# ESP32Shield.net
KiCad netlist of a schematic drawn in EAGLE
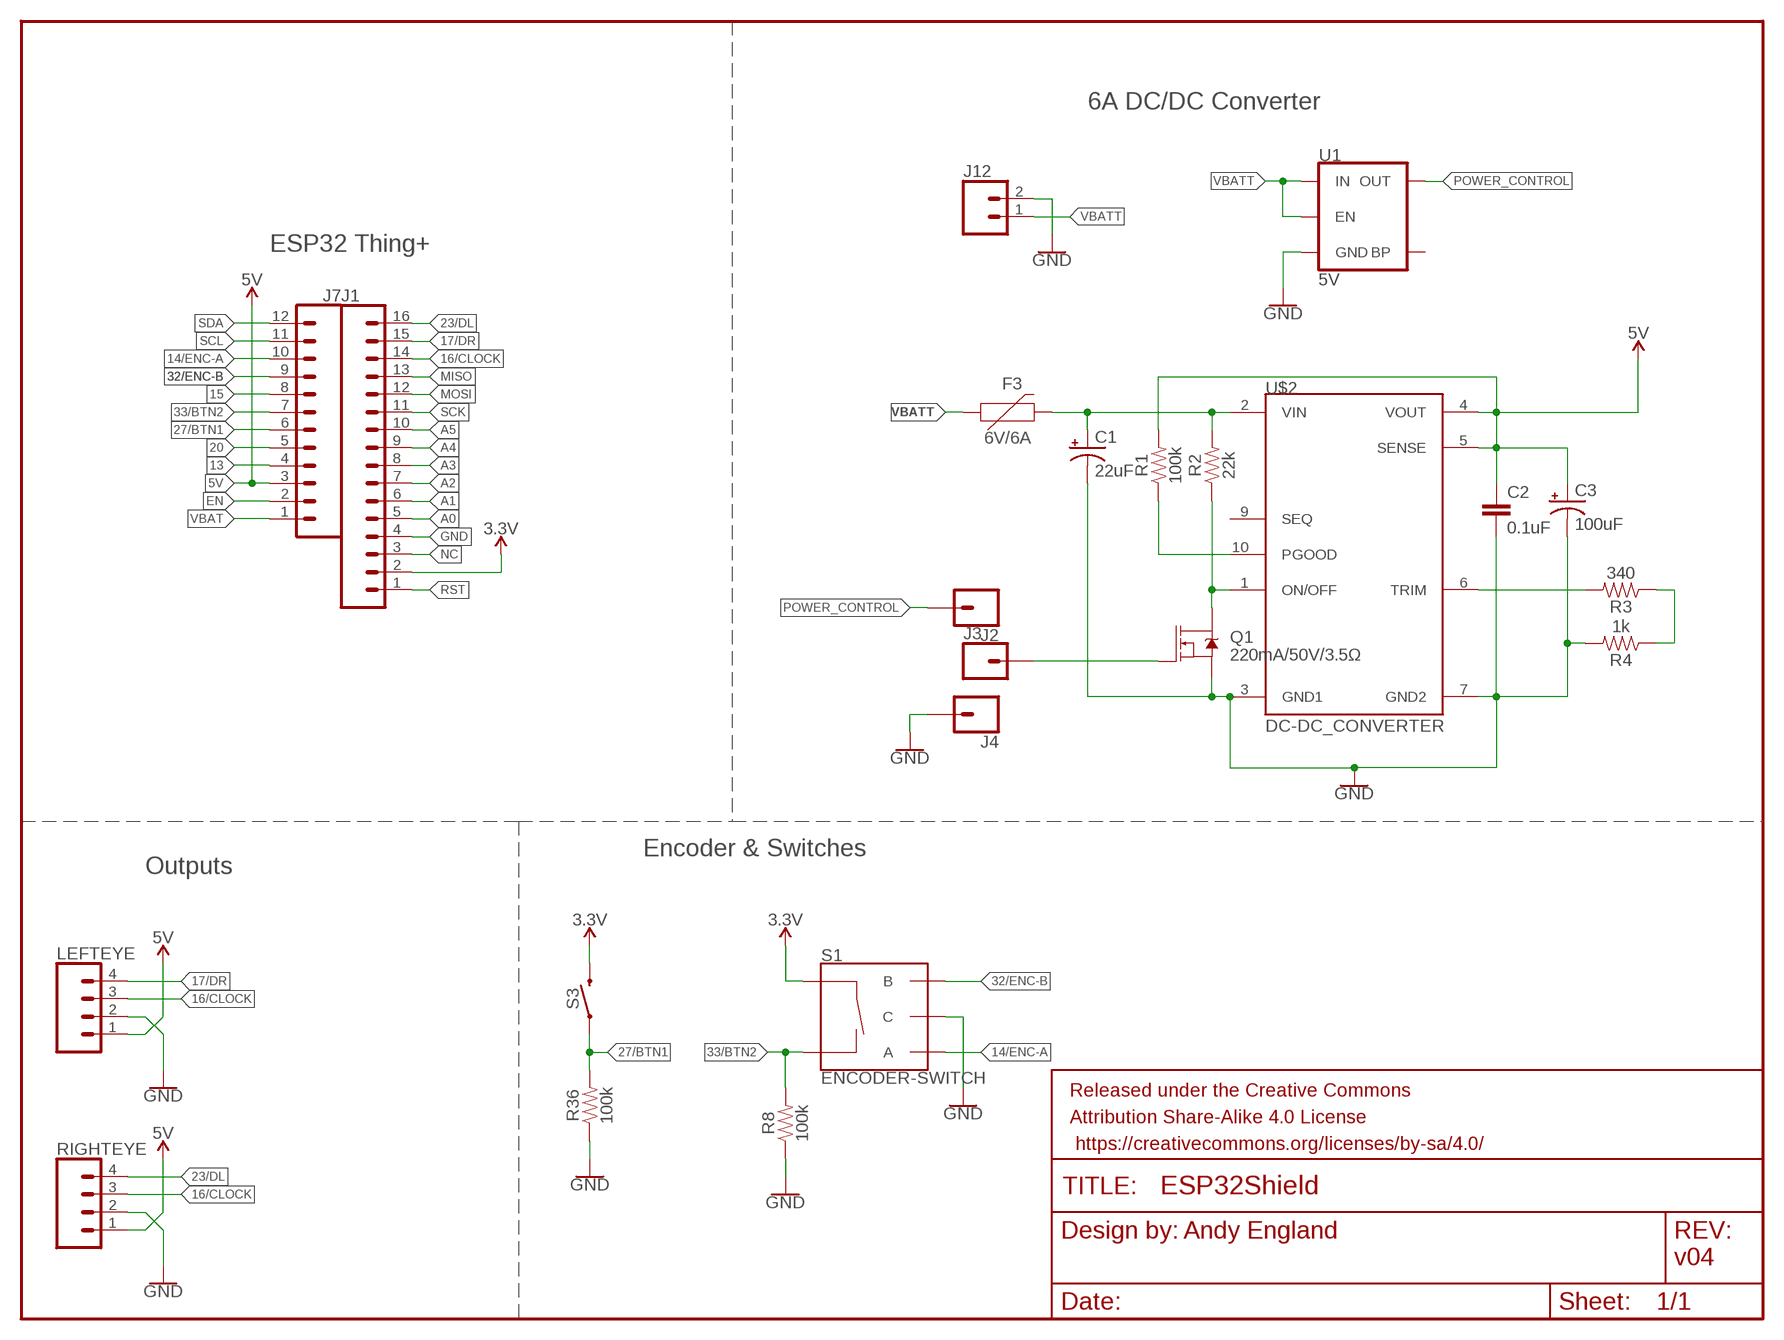
[diagram p0: schematic, sheet 1]

(export (version "E")
  (design (tool "Eeschema 10.0.6"))
  (components
    (comp (ref "C1")
      (value "22uF")
      (footprint "eagle-import:PANASONIC_C")
      (libsource (lib "eagle-import") (part "22UF-POLAR-PANASONIC_C-35V-20%"))
    )
    (comp (ref "C2")
      (value "0.1uF")
      (footprint "eagle-import:0603")
      (libsource (lib "eagle-import") (part "0.1UF-0603-25V-5%"))
    )
    (comp (ref "C3")
      (value "100uF")
      (footprint "eagle-import:PANASONIC_D")
      (libsource (lib "eagle-import") (part "100UF-POLAR-25V-20%(ELEC)"))
    )
    (comp (ref "F3")
      (value "6V/6A")
      (footprint "eagle-import:1206")
      (libsource (lib "eagle-import") (part "PPTC_HALF-AMP"))
    )
    (comp (ref "FRAME1")
      (value "FRAME-LETTER")
      (footprint "eagle-import:CREATIVE_COMMONS")
      (libsource (lib "eagle-import") (part "FRAME-LETTER"))
    )
    (comp (ref "J1")
      (value "CONN_161X16_NO_SILK")
      (footprint "eagle-import:1X16_NO_SILK")
      (libsource (lib "eagle-import") (part "CONN_161X16_NO_SILK"))
    )
    (comp (ref "J2")
      (value "CONN_01")
      (footprint "eagle-import:1X01")
      (libsource (lib "eagle-import") (part "CONN_01"))
    )
    (comp (ref "J3")
      (value "CONN_01")
      (footprint "eagle-import:1X01")
      (libsource (lib "eagle-import") (part "CONN_01"))
    )
    (comp (ref "J4")
      (value "CONN_01")
      (footprint "eagle-import:1X01")
      (libsource (lib "eagle-import") (part "CONN_01"))
    )
    (comp (ref "J7")
      (value "CONN_12NO_SILK")
      (footprint "eagle-import:1X12_NO_SILK")
      (libsource (lib "eagle-import") (part "CONN_12NO_SILK"))
    )
    (comp (ref "J12")
      (value "CONN_025MM")
      (footprint "eagle-import:SCREWTERMINAL-5MM-2")
      (libsource (lib "eagle-import") (part "CONN_025MM"))
    )
    (comp (ref "LEFTEYE")
      (value "CONN_041X04_NO_SILK")
      (footprint "eagle-import:1X04_NO_SILK")
      (libsource (lib "eagle-import") (part "CONN_041X04_NO_SILK"))
    )
    (comp (ref "Q1")
      (value "220mA/50V/3.5Ω")
      (footprint "eagle-import:SOT23-3")
      (libsource (lib "eagle-import") (part "MOSFET-NCH-BSS138"))
    )
    (comp (ref "R1")
      (value "100k")
      (footprint "eagle-import:0603")
      (libsource (lib "eagle-import") (part "100KOHM-0603-1/10W-1%"))
    )
    (comp (ref "R2")
      (value "22k")
      (footprint "eagle-import:0603")
      (libsource (lib "eagle-import") (part "22KOHM-0603-1/10W-1%"))
    )
    (comp (ref "R3")
      (value "340")
      (footprint "eagle-import:0603")
      (libsource (lib "eagle-import") (part "340OHM-0603-1/10W-1%"))
    )
    (comp (ref "R4")
      (value "1k")
      (footprint "eagle-import:0603")
      (libsource (lib "eagle-import") (part "1KOHM-0603-1/10W-1%"))
    )
    (comp (ref "R8")
      (value "100k")
      (footprint "eagle-import:0603")
      (libsource (lib "eagle-import") (part "100KOHM-0603-1/10W-1%"))
    )
    (comp (ref "R36")
      (value "100k")
      (footprint "eagle-import:0603")
      (libsource (lib "eagle-import") (part "100KOHM-0603-1/10W-1%"))
    )
    (comp (ref "RIGHTEYE")
      (value "CONN_041X04_NO_SILK")
      (footprint "eagle-import:1X04_NO_SILK")
      (libsource (lib "eagle-import") (part "CONN_041X04_NO_SILK"))
    )
    (comp (ref "S1")
      (value "ENCODER-SWITCH")
      (footprint "eagle-import:ROTARY_ENC_PLAIN")
      (libsource (lib "eagle-import") (part "ENCODER-SWITCH"))
    )
    (comp (ref "S3")
      (value "MOMENTARY-SWITCH-SPST-SMD-5.2-REDUNDANT")
      (footprint "eagle-import:TACTILE_SWITCH_SMD_5.2MM")
      (libsource (lib "eagle-import") (part "MOMENTARY-SWITCH-SPST-SMD-5.2-REDUNDANT"))
    )
    (comp (ref "U$2")
      (value "DC-DC_CONVERTER")
      (footprint "eagle-import:DC-DC_CONVERTER")
      (libsource (lib "eagle-import") (part "DC-DC_CONVERTER"))
    )
    (comp (ref "U1")
      (value "5V")
      (footprint "eagle-import:SOT23-5")
      (libsource (lib "eagle-import") (part "V_REG_MIC52055V"))
    )
  )
  (nets
    (net (code "1") (name "3.3V") (class "Default")
      (node (ref "J1") (pin "2") (pinfunction "2_2") (pintype "passive"))
      (node (ref "S1") (pin "SW+") (pinfunction "SW+_SW+") (pintype "bidirectional"))
      (node (ref "S3") (pin "3") (pinfunction "2_3") (pintype "passive"))
      (node (ref "S3") (pin "4") (pinfunction "2_4") (pintype "passive"))
    )
    (net (code "2") (name "5V") (class "Default")
      (node (ref "C2") (pin "1") (pinfunction "1_1") (pintype "passive"))
      (node (ref "C3") (pin "+") (pinfunction "+_+") (pintype "passive"))
      (node (ref "J7") (pin "3") (pinfunction "3_3") (pintype "passive"))
      (node (ref "LEFTEYE") (pin "1") (pinfunction "1_1") (pintype "passive"))
      (node (ref "R1") (pin "2") (pinfunction "2_2") (pintype "passive"))
      (node (ref "RIGHTEYE") (pin "1") (pinfunction "1_1") (pintype "passive"))
      (node (ref "U$2") (pin "4") (pinfunction "VOUT_4") (pintype "bidirectional"))
      (node (ref "U$2") (pin "5") (pinfunction "SENSE_5") (pintype "bidirectional"))
    )
    (net (code "3") (name "13") (class "Default")
      (node (ref "J7") (pin "4") (pinfunction "4_4") (pintype "passive"))
    )
    (net (code "4") (name "14{slash}ENC-A") (class "Default")
      (node (ref "J7") (pin "10") (pinfunction "10_10") (pintype "passive"))
      (node (ref "S1") (pin "A") (pinfunction "A_A") (pintype "bidirectional"))
    )
    (net (code "5") (name "15") (class "Default")
      (node (ref "J7") (pin "8") (pinfunction "8_8") (pintype "passive"))
    )
    (net (code "6") (name "16{slash}CLOCK") (class "Default")
      (node (ref "J1") (pin "14") (pinfunction "14_14") (pintype "passive"))
      (node (ref "LEFTEYE") (pin "3") (pinfunction "3_3") (pintype "passive"))
      (node (ref "RIGHTEYE") (pin "3") (pinfunction "3_3") (pintype "passive"))
    )
    (net (code "7") (name "17{slash}DR") (class "Default")
      (node (ref "J1") (pin "15") (pinfunction "15_15") (pintype "passive"))
      (node (ref "LEFTEYE") (pin "4") (pinfunction "4_4") (pintype "passive"))
    )
    (net (code "8") (name "20") (class "Default")
      (node (ref "J7") (pin "5") (pinfunction "5_5") (pintype "passive"))
    )
    (net (code "9") (name "23{slash}DL") (class "Default")
      (node (ref "J1") (pin "16") (pinfunction "16_16") (pintype "passive"))
      (node (ref "RIGHTEYE") (pin "4") (pinfunction "4_4") (pintype "passive"))
    )
    (net (code "10") (name "27{slash}BTN1") (class "Default")
      (node (ref "J7") (pin "6") (pinfunction "6_6") (pintype "passive"))
      (node (ref "R36") (pin "2") (pinfunction "2_2") (pintype "passive"))
      (node (ref "S3") (pin "1") (pinfunction "1_1") (pintype "passive"))
      (node (ref "S3") (pin "2") (pinfunction "1_2") (pintype "passive"))
    )
    (net (code "11") (name "32{slash}ENC-B") (class "Default")
      (node (ref "J7") (pin "9") (pinfunction "9_9") (pintype "passive"))
      (node (ref "S1") (pin "B") (pinfunction "B_B") (pintype "bidirectional"))
    )
    (net (code "12") (name "33{slash}BTN2") (class "Default")
      (node (ref "J7") (pin "7") (pinfunction "7_7") (pintype "passive"))
      (node (ref "R8") (pin "2") (pinfunction "2_2") (pintype "passive"))
      (node (ref "S1") (pin "SW-") (pinfunction "SW-_SW-") (pintype "bidirectional"))
    )
    (net (code "13") (name "A0") (class "Default")
      (node (ref "J1") (pin "5") (pinfunction "5_5") (pintype "passive"))
    )
    (net (code "14") (name "A1") (class "Default")
      (node (ref "J1") (pin "6") (pinfunction "6_6") (pintype "passive"))
    )
    (net (code "15") (name "A2") (class "Default")
      (node (ref "J1") (pin "7") (pinfunction "7_7") (pintype "passive"))
    )
    (net (code "16") (name "A3") (class "Default")
      (node (ref "J1") (pin "8") (pinfunction "8_8") (pintype "passive"))
    )
    (net (code "17") (name "A4") (class "Default")
      (node (ref "J1") (pin "9") (pinfunction "9_9") (pintype "passive"))
    )
    (net (code "18") (name "A5") (class "Default")
      (node (ref "J1") (pin "10") (pinfunction "10_10") (pintype "passive"))
    )
    (net (code "19") (name "EN") (class "Default")
      (node (ref "J7") (pin "2") (pinfunction "2_2") (pintype "passive"))
    )
    (net (code "20") (name "GND") (class "Default")
      (node (ref "C1") (pin "-") (pinfunction "-_-") (pintype "passive"))
      (node (ref "C2") (pin "2") (pinfunction "2_2") (pintype "passive"))
      (node (ref "C3") (pin "-") (pinfunction "-_-") (pintype "passive"))
      (node (ref "J1") (pin "4") (pinfunction "4_4") (pintype "passive"))
      (node (ref "J12") (pin "2") (pinfunction "2_2") (pintype "passive"))
      (node (ref "J4") (pin "1") (pinfunction "1_1") (pintype "passive"))
      (node (ref "LEFTEYE") (pin "2") (pinfunction "2_2") (pintype "passive"))
      (node (ref "Q1") (pin "2") (pinfunction "S_2") (pintype "bidirectional"))
      (node (ref "R36") (pin "1") (pinfunction "1_1") (pintype "passive"))
      (node (ref "R4") (pin "2") (pinfunction "2_2") (pintype "passive"))
      (node (ref "R8") (pin "1") (pinfunction "1_1") (pintype "passive"))
      (node (ref "RIGHTEYE") (pin "2") (pinfunction "2_2") (pintype "passive"))
      (node (ref "S1") (pin "C") (pinfunction "C_C") (pintype "bidirectional"))
      (node (ref "U$2") (pin "3") (pinfunction "GND1_3") (pintype "bidirectional"))
      (node (ref "U$2") (pin "7") (pinfunction "GND2_7") (pintype "bidirectional"))
      (node (ref "U1") (pin "2") (pinfunction "GND_2") (pintype "input"))
    )
    (net (code "21") (name "MISO") (class "Default")
      (node (ref "J1") (pin "13") (pinfunction "13_13") (pintype "passive"))
    )
    (net (code "22") (name "MOSI") (class "Default")
      (node (ref "J1") (pin "12") (pinfunction "12_12") (pintype "passive"))
    )
    (net (code "23") (name "NC") (class "Default")
      (node (ref "J1") (pin "3") (pinfunction "3_3") (pintype "passive"))
    )
    (net (code "24") (name "Net-(Q1-D)") (class "Default")
      (node (ref "Q1") (pin "3") (pinfunction "D_3") (pintype "bidirectional"))
      (node (ref "R2") (pin "1") (pinfunction "1_1") (pintype "passive"))
      (node (ref "U$2") (pin "1") (pinfunction "ON/OFF_1") (pintype "bidirectional"))
    )
    (net (code "25") (name "Net-(Q1-G)") (class "Default")
      (node (ref "J3") (pin "1") (pinfunction "1_1") (pintype "passive"))
      (node (ref "Q1") (pin "1") (pinfunction "G_1") (pintype "bidirectional"))
    )
    (net (code "26") (name "Net-(R3-Pad1)") (class "Default")
      (node (ref "R3") (pin "1") (pinfunction "1_1") (pintype "passive"))
      (node (ref "R4") (pin "1") (pinfunction "1_1") (pintype "passive"))
    )
    (net (code "27") (name "Net-(U$2-PGOOD)") (class "Default")
      (node (ref "R1") (pin "1") (pinfunction "1_1") (pintype "passive"))
      (node (ref "U$2") (pin "10") (pinfunction "PGOOD_10") (pintype "bidirectional"))
    )
    (net (code "28") (name "Net-(U$2-TRIM)") (class "Default")
      (node (ref "R3") (pin "2") (pinfunction "2_2") (pintype "passive"))
      (node (ref "U$2") (pin "6") (pinfunction "TRIM_6") (pintype "bidirectional"))
    )
    (net (code "29") (name "Net-(U$2-VIN)") (class "Default")
      (node (ref "C1") (pin "+") (pinfunction "+_+") (pintype "passive"))
      (node (ref "F3") (pin "2") (pinfunction "2_2") (pintype "bidirectional"))
      (node (ref "R2") (pin "2") (pinfunction "2_2") (pintype "passive"))
      (node (ref "U$2") (pin "2") (pinfunction "VIN_2") (pintype "bidirectional"))
    )
    (net (code "30") (name "POWER_CONTROL") (class "Default")
      (node (ref "J2") (pin "1") (pinfunction "1_1") (pintype "passive"))
      (node (ref "U1") (pin "5") (pinfunction "OUT_5") (pintype "passive"))
    )
    (net (code "31") (name "RST") (class "Default")
      (node (ref "J1") (pin "1") (pinfunction "1_1") (pintype "passive"))
    )
    (net (code "32") (name "SCK") (class "Default")
      (node (ref "J1") (pin "11") (pinfunction "11_11") (pintype "passive"))
    )
    (net (code "33") (name "SCL") (class "Default")
      (node (ref "J7") (pin "11") (pinfunction "11_11") (pintype "passive"))
    )
    (net (code "34") (name "SDA") (class "Default")
      (node (ref "J7") (pin "12") (pinfunction "12_12") (pintype "passive"))
    )
    (net (code "35") (name "VBAT") (class "Default")
      (node (ref "J7") (pin "1") (pinfunction "1_1") (pintype "passive"))
    )
    (net (code "36") (name "VBATT") (class "Default")
      (node (ref "F3") (pin "1") (pinfunction "1_1") (pintype "bidirectional"))
      (node (ref "J12") (pin "1") (pinfunction "1_1") (pintype "passive"))
      (node (ref "U1") (pin "1") (pinfunction "IN_1") (pintype "input"))
      (node (ref "U1") (pin "3") (pinfunction "EN_3") (pintype "input"))
    )
    (net (code "37") (name "unconnected-(U$2-SEQ-Pad9)") (class "Default")
      (node (ref "U$2") (pin "9") (pinfunction "SEQ_9") (pintype "bidirectional"))
    )
    (net (code "38") (name "unconnected-(U1-BP-Pad4)") (class "Default")
      (node (ref "U1") (pin "4") (pinfunction "BP_4") (pintype "input"))
    )
  )
)
